# RJ12Breakout.net
KiCad netlist of a schematic drawn in EAGLE
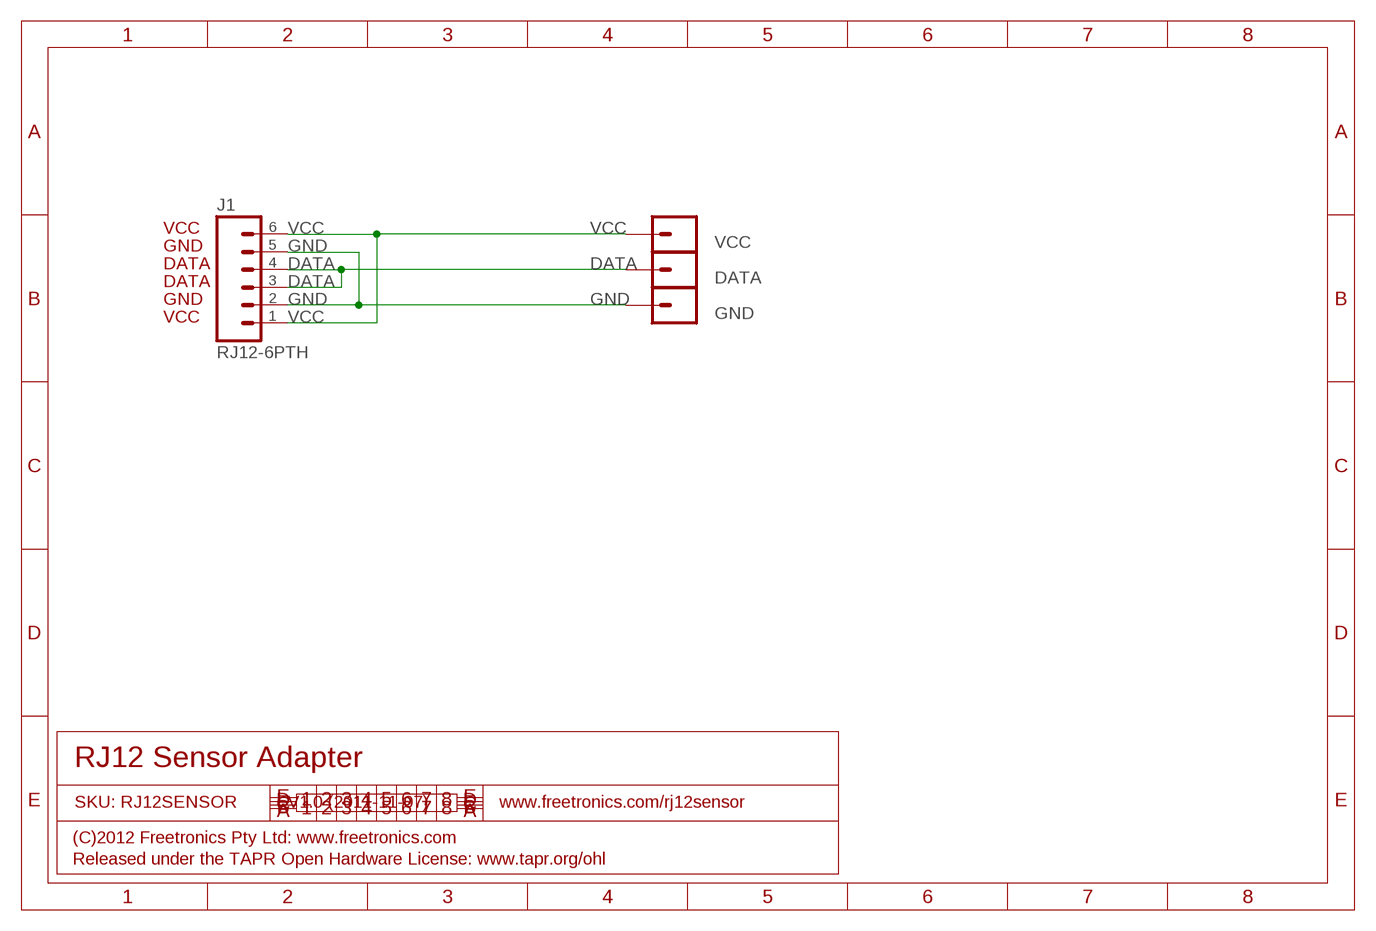
[diagram p0: schematic, sheet 1]

(export (version "E")
  (design (tool "Eeschema 10.0.6"))
  (components
    (comp (ref "DATA")
      (value "M01PTH")
      (footprint "eagle-import:1X01")
      (libsource (lib "eagle-import") (part "M01PTH"))
    )
    (comp (ref "GND")
      (value "M01PTH")
      (footprint "eagle-import:1X01")
      (libsource (lib "eagle-import") (part "M01PTH"))
    )
    (comp (ref "J1")
      (value "RJ12-6PTH")
      (footprint "eagle-import:RJ12-6")
      (libsource (lib "eagle-import") (part "RJ12-6PTH"))
    )
    (comp (ref "VCC")
      (value "M01PTH")
      (footprint "eagle-import:1X01")
      (libsource (lib "eagle-import") (part "M01PTH"))
    )
  )
  (nets
    (net (code "1") (name "/DATA") (class "Default")
      (node (ref "DATA") (pin "1") (pinfunction "1_1") (pintype "passive"))
      (node (ref "J1") (pin "3") (pinfunction "3_3") (pintype "passive"))
      (node (ref "J1") (pin "4") (pinfunction "4_4") (pintype "passive"))
    )
    (net (code "2") (name "/GND") (class "Default")
      (node (ref "GND") (pin "1") (pinfunction "1_1") (pintype "passive"))
      (node (ref "J1") (pin "2") (pinfunction "2_2") (pintype "passive"))
      (node (ref "J1") (pin "5") (pinfunction "5_5") (pintype "passive"))
    )
    (net (code "3") (name "/VCC") (class "Default")
      (node (ref "J1") (pin "1") (pinfunction "1_1") (pintype "passive"))
      (node (ref "J1") (pin "6") (pinfunction "6_6") (pintype "passive"))
      (node (ref "VCC") (pin "1") (pinfunction "1_1") (pintype "passive"))
    )
  )
)
